# MCU.net
KiCad netlist of a schematic drawn in Altium Designer
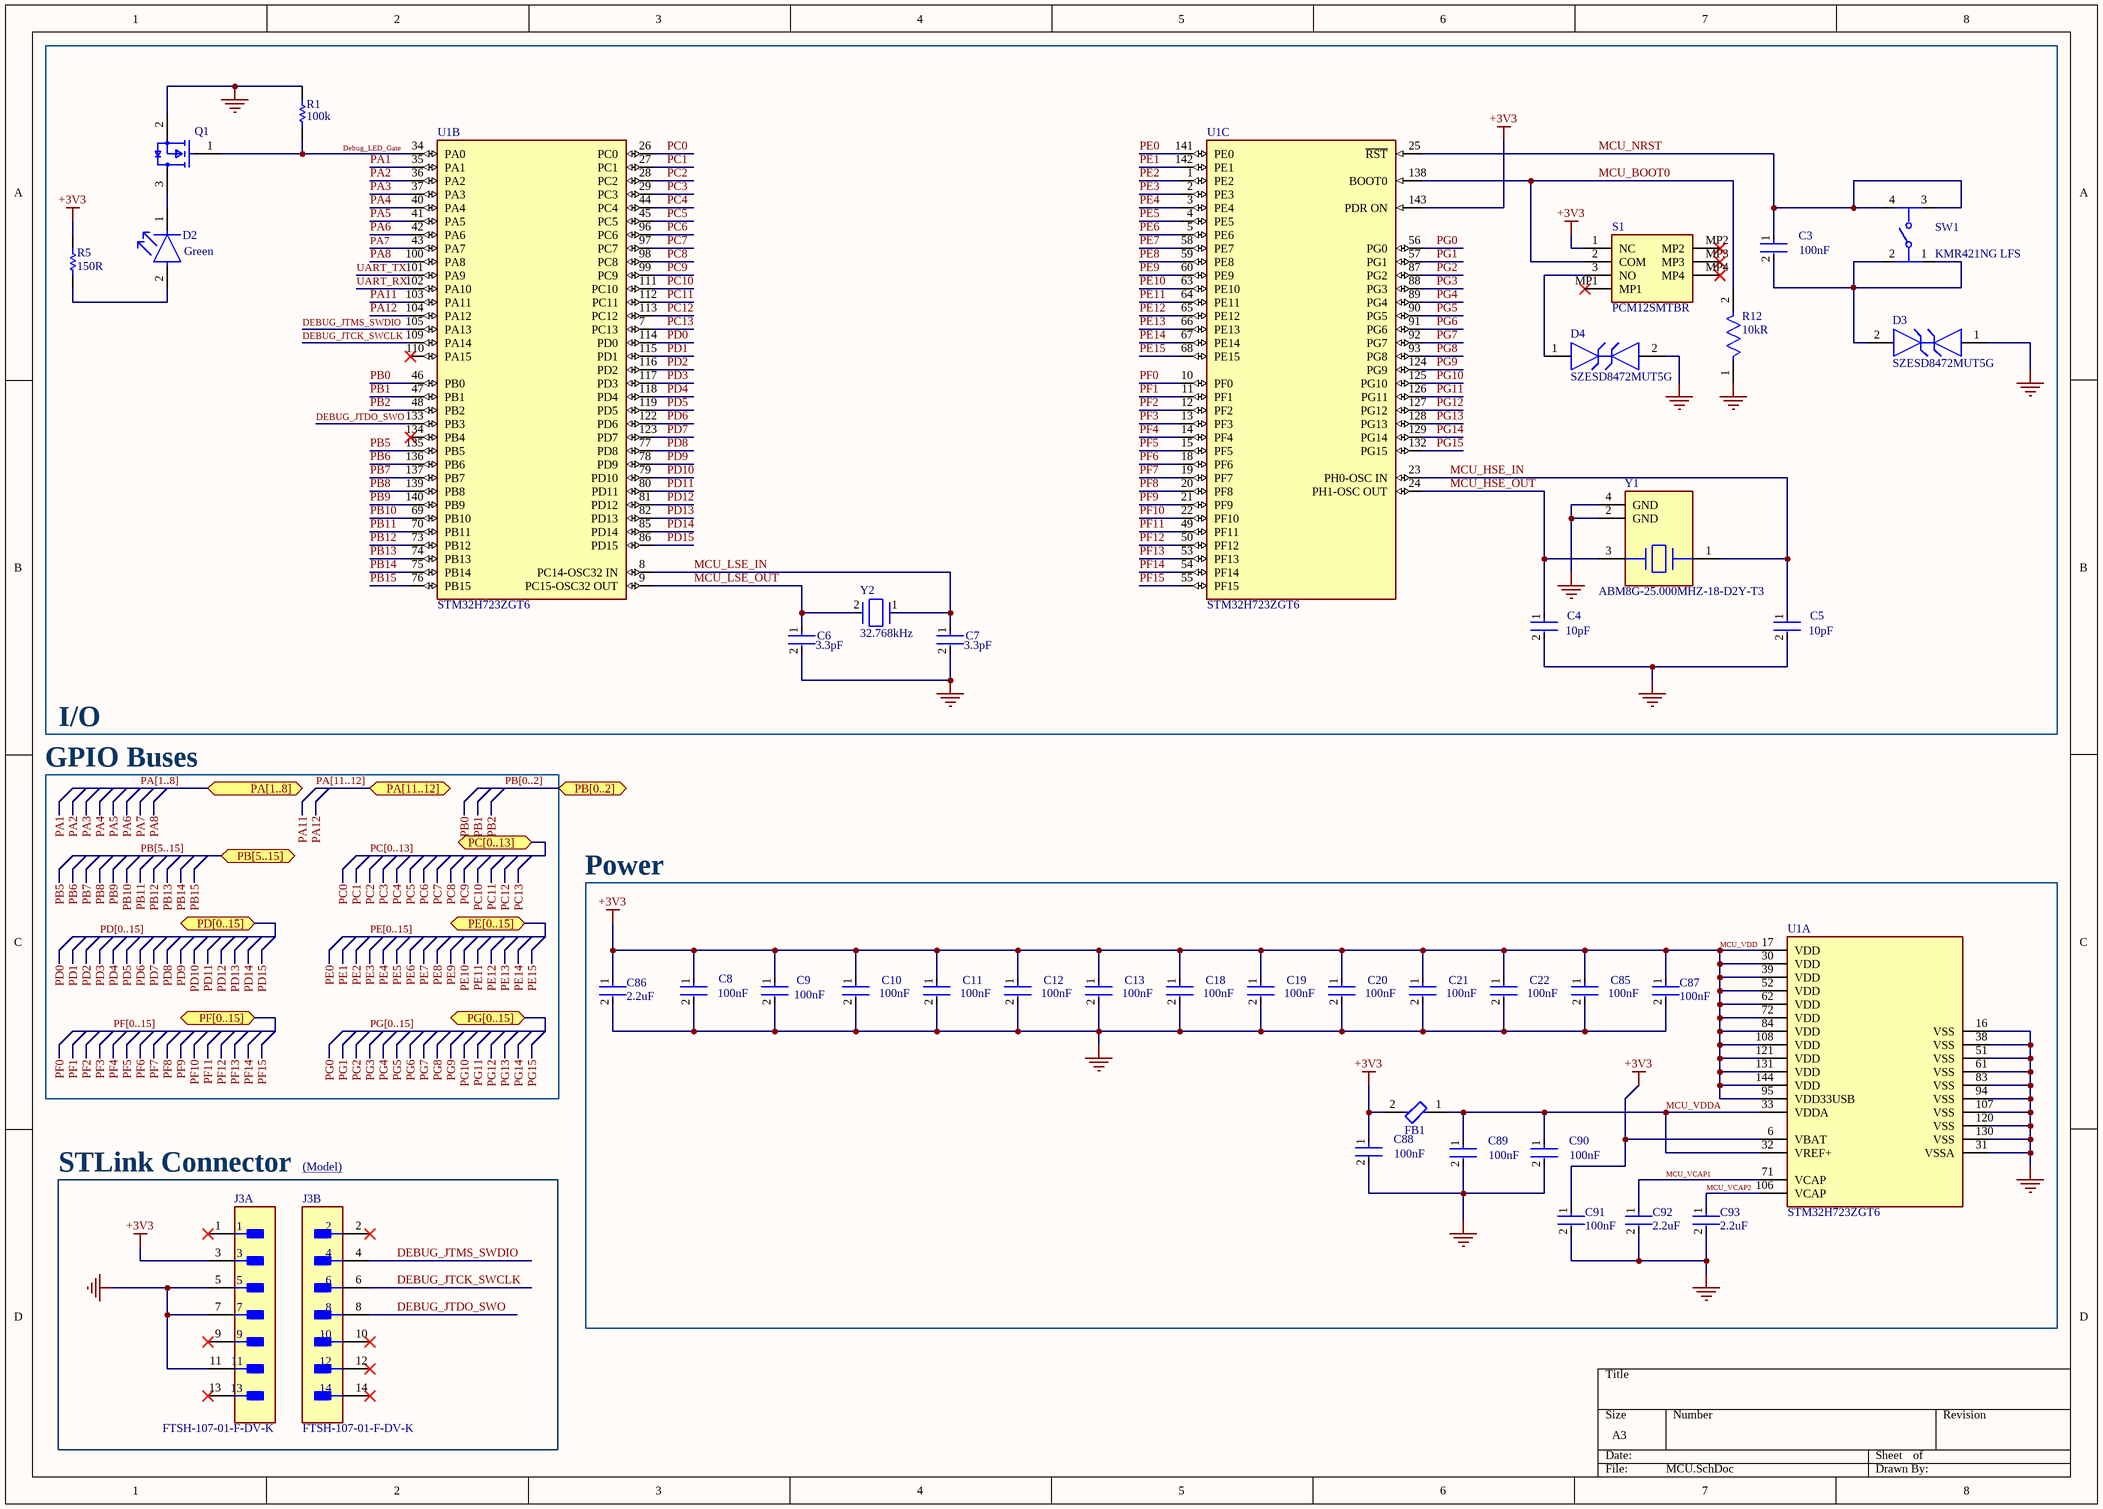
[diagram p0: MCU.SchDoc]

(export (version "E")
  (design (tool "Eeschema 10.0.6"))
  (components
    (comp (ref "C3")
      (value "GCM155R71H104ME02J")
      (footprint "FP-GCM155-0_05-IPC_A")
      (description "Ceramic Capacitor for Automotive 100nF ±20% 50VDC X7R 0402 Paper T/R")
      (fields (field (name "CAPACITANCE") "100nF"))
      (libsource (lib "Altium Content Vault") (part "02cd4be3c70576c341d710602a673aa"))
    )
    (comp (ref "C4")
      (value "GCM1555G1H100GA16D")
      (footprint "FP-GCM155-0_05-IPC_B")
      (description "Ceramic Capacitor for Automotive 10pF ±2% 50VDC X8G 0402 Paper T/R")
      (fields (field (name "CAPACITANCE") "10pF"))
      (libsource (lib "Altium Content Vault") (part "02cd4be3c70576c341d710602a673aa"))
    )
    (comp (ref "C5")
      (value "GCM1555G1H100GA16D")
      (footprint "FP-GCM155-0_05-IPC_B")
      (description "Ceramic Capacitor for Automotive 10pF ±2% 50VDC X8G 0402 Paper T/R")
      (fields (field (name "CAPACITANCE") "10pF"))
      (libsource (lib "Altium Content Vault") (part "02cd4be3c70576c341d710602a673aa"))
    )
    (comp (ref "C6")
      (value "GCM1555C1H3R3CA16J")
      (footprint "FP-GCM155-0_05-IPC_C")
      (description "Ceramic Capacitor for Automotive 3.3pF ±0.25pF 50VDC C0G 0402 Paper T/R")
      (fields (field (name "CAPACITANCE") "3.3pF"))
      (libsource (lib "Altium Content Vault") (part "02cd4be3c70576c341d710602a673aa"))
    )
    (comp (ref "C7")
      (value "GCM1555C1H3R3CA16J")
      (footprint "FP-GCM155-0_05-IPC_C")
      (description "Ceramic Capacitor for Automotive 3.3pF ±0.25pF 50VDC C0G 0402 Paper T/R")
      (fields (field (name "CAPACITANCE") "3.3pF"))
      (libsource (lib "Altium Content Vault") (part "02cd4be3c70576c341d710602a673aa"))
    )
    (comp (ref "C8")
      (value "GCM155R71H104ME02J")
      (footprint "FP-GCM155-0_05-IPC_A")
      (description "Ceramic Capacitor for Automotive 100nF ±20% 50VDC X7R 0402 Paper T/R")
      (fields (field (name "CAPACITANCE") "100nF"))
      (libsource (lib "Altium Content Vault") (part "02cd4be3c70576c341d710602a673aa"))
    )
    (comp (ref "C9")
      (value "GCM155R71H104ME02J")
      (footprint "FP-GCM155-0_05-IPC_A")
      (description "Ceramic Capacitor for Automotive 100nF ±20% 50VDC X7R 0402 Paper T/R")
      (fields (field (name "CAPACITANCE") "100nF"))
      (libsource (lib "Altium Content Vault") (part "02cd4be3c70576c341d710602a673aa"))
    )
    (comp (ref "C10")
      (value "GCM155R71H104ME02J")
      (footprint "FP-GCM155-0_05-IPC_A")
      (description "Ceramic Capacitor for Automotive 100nF ±20% 50VDC X7R 0402 Paper T/R")
      (fields (field (name "CAPACITANCE") "100nF"))
      (libsource (lib "Altium Content Vault") (part "02cd4be3c70576c341d710602a673aa"))
    )
    (comp (ref "C11")
      (value "GCM155R71H104ME02J")
      (footprint "FP-GCM155-0_05-IPC_A")
      (description "Ceramic Capacitor for Automotive 100nF ±20% 50VDC X7R 0402 Paper T/R")
      (fields (field (name "CAPACITANCE") "100nF"))
      (libsource (lib "Altium Content Vault") (part "02cd4be3c70576c341d710602a673aa"))
    )
    (comp (ref "C12")
      (value "GCM155R71H104ME02J")
      (footprint "FP-GCM155-0_05-IPC_A")
      (description "Ceramic Capacitor for Automotive 100nF ±20% 50VDC X7R 0402 Paper T/R")
      (fields (field (name "CAPACITANCE") "100nF"))
      (libsource (lib "Altium Content Vault") (part "02cd4be3c70576c341d710602a673aa"))
    )
    (comp (ref "C13")
      (value "GCM155R71H104ME02J")
      (footprint "FP-GCM155-0_05-IPC_A")
      (description "Ceramic Capacitor for Automotive 100nF ±20% 50VDC X7R 0402 Paper T/R")
      (fields (field (name "CAPACITANCE") "100nF"))
      (libsource (lib "Altium Content Vault") (part "02cd4be3c70576c341d710602a673aa"))
    )
    (comp (ref "C18")
      (value "GCM155R71H104ME02J")
      (footprint "FP-GCM155-0_05-IPC_A")
      (description "Ceramic Capacitor for Automotive 100nF ±20% 50VDC X7R 0402 Paper T/R")
      (fields (field (name "CAPACITANCE") "100nF"))
      (libsource (lib "Altium Content Vault") (part "02cd4be3c70576c341d710602a673aa"))
    )
    (comp (ref "C19")
      (value "GCM155R71H104ME02J")
      (footprint "FP-GCM155-0_05-IPC_A")
      (description "Ceramic Capacitor for Automotive 100nF ±20% 50VDC X7R 0402 Paper T/R")
      (fields (field (name "CAPACITANCE") "100nF"))
      (libsource (lib "Altium Content Vault") (part "02cd4be3c70576c341d710602a673aa"))
    )
    (comp (ref "C20")
      (value "GCM155R71H104ME02J")
      (footprint "FP-GCM155-0_05-IPC_A")
      (description "Ceramic Capacitor for Automotive 100nF ±20% 50VDC X7R 0402 Paper T/R")
      (fields (field (name "CAPACITANCE") "100nF"))
      (libsource (lib "Altium Content Vault") (part "02cd4be3c70576c341d710602a673aa"))
    )
    (comp (ref "C21")
      (value "GCM155R71H104ME02J")
      (footprint "FP-GCM155-0_05-IPC_A")
      (description "Ceramic Capacitor for Automotive 100nF ±20% 50VDC X7R 0402 Paper T/R")
      (fields (field (name "CAPACITANCE") "100nF"))
      (libsource (lib "Altium Content Vault") (part "02cd4be3c70576c341d710602a673aa"))
    )
    (comp (ref "C22")
      (value "GCM155R71H104ME02J")
      (footprint "FP-GCM155-0_05-IPC_A")
      (description "Ceramic Capacitor for Automotive 100nF ±20% 50VDC X7R 0402 Paper T/R")
      (fields (field (name "CAPACITANCE") "100nF"))
      (libsource (lib "Altium Content Vault") (part "02cd4be3c70576c341d710602a673aa"))
    )
    (comp (ref "C85")
      (value "GCM155R71H104ME02J")
      (footprint "FP-GCM155-0_05-IPC_A")
      (description "Ceramic Capacitor for Automotive 100nF ±20% 50VDC X7R 0402 Paper T/R")
      (fields (field (name "CAPACITANCE") "100nF"))
      (libsource (lib "Altium Content Vault") (part "02cd4be3c70576c341d710602a673aa"))
    )
    (comp (ref "C86")
      (value "GCM188C71A225KE02D")
      (footprint "FP-GCH188-0_1-e0_2_0_5-MFG")
      (description "GCM188C71A225KE02D Multilayer Ceramic Capacitor, 2.2 uF, 10 V, ± 10%, X7S, 0603 [1608 Metric]")
      (fields (field (name "CAPACITANCE") "2.2uF"))
      (libsource (lib "Altium Content Vault") (part "b4654b650e69147ec39a6b967a45e02"))
    )
    (comp (ref "C87")
      (value "GCM155R71H104ME02J")
      (footprint "FP-GCM155-0_05-IPC_A")
      (description "Ceramic Capacitor for Automotive 100nF ±20% 50VDC X7R 0402 Paper T/R")
      (fields (field (name "CAPACITANCE") "100nF"))
      (libsource (lib "Altium Content Vault") (part "02cd4be3c70576c341d710602a673aa"))
    )
    (comp (ref "C88")
      (value "GCM155R71H104ME02J")
      (footprint "FP-GCM155-0_05-IPC_A")
      (description "Ceramic Capacitor for Automotive 100nF ±20% 50VDC X7R 0402 Paper T/R")
      (fields (field (name "CAPACITANCE") "100nF"))
      (libsource (lib "Altium Content Vault") (part "02cd4be3c70576c341d710602a673aa"))
    )
    (comp (ref "C89")
      (value "GCM155R71H104ME02J")
      (footprint "FP-GCM155-0_05-IPC_A")
      (description "Ceramic Capacitor for Automotive 100nF ±20% 50VDC X7R 0402 Paper T/R")
      (fields (field (name "CAPACITANCE") "100nF"))
      (libsource (lib "Altium Content Vault") (part "02cd4be3c70576c341d710602a673aa"))
    )
    (comp (ref "C90")
      (value "GCM155R71H104ME02J")
      (footprint "FP-GCM155-0_05-IPC_A")
      (description "Ceramic Capacitor for Automotive 100nF ±20% 50VDC X7R 0402 Paper T/R")
      (fields (field (name "CAPACITANCE") "100nF"))
      (libsource (lib "Altium Content Vault") (part "02cd4be3c70576c341d710602a673aa"))
    )
    (comp (ref "C91")
      (value "GCM155R71H104ME02J")
      (footprint "FP-GCM155-0_05-IPC_A")
      (description "Ceramic Capacitor for Automotive 100nF ±20% 50VDC X7R 0402 Paper T/R")
      (fields (field (name "CAPACITANCE") "100nF"))
      (libsource (lib "Altium Content Vault") (part "02cd4be3c70576c341d710602a673aa"))
    )
    (comp (ref "C92")
      (value "GCM188C71A225KE02D")
      (footprint "FP-GCH188-0_1-e0_2_0_5-MFG")
      (description "GCM188C71A225KE02D Multilayer Ceramic Capacitor, 2.2 uF, 10 V, ± 10%, X7S, 0603 [1608 Metric]")
      (fields (field (name "CAPACITANCE") "2.2uF"))
      (libsource (lib "Altium Content Vault") (part "b4654b650e69147ec39a6b967a45e02"))
    )
    (comp (ref "C93")
      (value "GCM188C71A225KE02D")
      (footprint "FP-GCH188-0_1-e0_2_0_5-MFG")
      (description "GCM188C71A225KE02D Multilayer Ceramic Capacitor, 2.2 uF, 10 V, ± 10%, X7S, 0603 [1608 Metric]")
      (fields (field (name "CAPACITANCE") "2.2uF"))
      (libsource (lib "Altium Content Vault") (part "b4654b650e69147ec39a6b967a45e02"))
    )
    (comp (ref "D2")
      (value "SML-P13PTT86R")
      (footprint "FP-SML-P1-MFG")
      (description "LED GREEN CLEAR 1006 SMD")
      (fields
        (field (name "MANUFACTURER") "Rohm")
        (field (name "OCTOPART") "https://octopart.com/sml-p13ptt86r-rohm-59370256")
        (field (name "COLOUR") "Green")
      )
      (libsource (lib "Altium Content Vault") (part "8706943c75ba83719d021d2fdc84c58"))
    )
    (comp (ref "D3")
      (value "SZESD8472MUT5G")
      (footprint "FP-152AF-MFG")
      (description "TVS DIODE 5.3V 14V 2X3DFN")
      (libsource (lib "Altium Content Vault") (part "9a4650ba5e636bd8b2e4c4fb393e9aa"))
    )
    (comp (ref "D4")
      (value "SZESD8472MUT5G")
      (footprint "FP-152AF-MFG")
      (description "TVS DIODE 5.3V 14V 2X3DFN")
      (libsource (lib "Altium Content Vault") (part "9a4650ba5e636bd8b2e4c4fb393e9aa"))
    )
    (comp (ref "FB1")
      (value "BLM15BX102SZ1D")
      (footprint "FP-BLM15-0_05-MFG")
      (description "Chip Ferrite Bead, 0402, 1000Ω @ 100MHz, 0.65Ω, 25%, 300mA")
      (libsource (lib "Altium Content Vault") (part "5f30dd21d616792df468990f7003faa"))
    )
    (comp (ref "J3")
      (value "FTSH-107-01-F-DV-K")
      (footprint "FP-FTSH-107-01-F-DV-K-MFG")
      (description "CONN HEADER SMD 14POS 1.27MM")
      (libsource (lib "") (part "ab214579d66ef07f87fa9c6f4e4f9ab_1"))
    )
    (comp (ref "Q1")
      (value "2N7002H6327XTSA2")
      (footprint "FP-PG-SOT23-3-MFG")
      (description "MOSFET N-CH 60V 0.3A SOT23")
      (libsource (lib "Altium Content Vault") (part "2d979dc9c009d20783d0745ce0ba7b4"))
    )
    (comp (ref "R1")
      (value "RC0402FR-07100KL")
      (footprint "RESC1005X40X25NL05T10")
      (fields (field (name "MANUFACTURER") "Yageo / Phycomp") (field (name "RESISTANCE") "100k"))
      (libsource (lib "Altium Content Vault") (part "RES"))
    )
    (comp (ref "R5")
      (value "RC0402JR-13150RL")
      (footprint "RESC1005X40X25LL05T10")
      (fields (field (name "MANUFACTURER") "Yageo") (field (name "RESISTANCE") "150R"))
      (libsource (lib "Altium Content Vault") (part "RES"))
    )
    (comp (ref "R12")
      (value "RC0402FR-1310KL")
      (footprint "FP-RC0402-0_4-IPC_A")
      (description "RESISTOR 0402 10K 1%")
      (fields (field (name "RESISTANCE") "10kR") (field (name "TOLERANCE") "1%"))
      (libsource (lib "Altium Content Vault") (part "1029c3af85768c4190bb7ad29bc67b5"))
    )
    (comp (ref "S1")
      (value "PCM12SMTBR")
      (footprint "PCM12SMTBR")
      (description "Switch")
      (fields (field (name "MOUSER PART NUMBER") "611-PCM12SMTBR"))
      (libsource (lib "audio_dev_pcb") (part "PCM12SMTBR"))
    )
    (comp (ref "SW1")
      (value "KMR421NG LFS")
      (footprint "FP-KMR421NG_LFS-MFG")
      (description "SWITCH TACTILE SPST-NO 0.05A 32V")
      (fields
        (field (name "MANUFACTURER") "C&K Components")
        (field (name "OCTOPART") "https://octopart.com/kmr421nglfs-c%26k+components-7226706")
      )
      (libsource (lib "Altium Content Vault") (part "82b636f13fd696edb7519609c0a8a76"))
    )
    (comp (ref "U1")
      (value "STM32H723ZGT6")
      (footprint "FP-LQFP144-1A-IPC_A")
      (description "IC MCU 32BIT 1MB FLASH 144LQFP")
      (libsource (lib "") (part "099c9e622ff36f7eb897f9cba6d1f51_1"))
    )
    (comp (ref "Y1")
      (value "ABM8G-25.000MHZ-18-D2Y-T3")
      (footprint "FP-ABM8G-MFG")
      (description "Crystal 25MHz ±20ppm (Tol) ±30ppm (Stability) 18pF FUND 60Ω 4-Pin SMD T/R")
      (fields (field (name "TOLERANCE") "20ppm"))
      (libsource (lib "Altium Content Vault") (part "48e526d86b7f2615d98721063c72f49"))
    )
    (comp (ref "Y2")
      (value "ECS-.327-6-34QCN-TR")
      (footprint "FP-ECX-34Q-MFG")
      (description "CRYSTAL 32.768KHZ 6PF SMD")
      (fields
        (field (name "OCTOPART") "https://octopart.com/ecs-.327-6-34qcn-tr-ecs+international-97157707")
        (field (name "MANUFACTURER") "ECS Inc.")
        (field (name "FREQUENCY") "32.768kHz")
      )
      (libsource (lib "Altium Content Vault") (part "99724985039315a44fd0d1401b84e49"))
    )
  )
  (nets
    (net (code "1") (name "+3V3") (class "Default")
      (node (ref "C10") (pin "1") (pinfunction "1_1") (pintype "passive"))
      (node (ref "C11") (pin "1") (pinfunction "1_1") (pintype "passive"))
      (node (ref "C12") (pin "1") (pinfunction "1_1") (pintype "passive"))
      (node (ref "C13") (pin "1") (pinfunction "1_1") (pintype "passive"))
      (node (ref "C18") (pin "1") (pinfunction "1_1") (pintype "passive"))
      (node (ref "C19") (pin "1") (pinfunction "1_1") (pintype "passive"))
      (node (ref "C20") (pin "1") (pinfunction "1_1") (pintype "passive"))
      (node (ref "C21") (pin "1") (pinfunction "1_1") (pintype "passive"))
      (node (ref "C22") (pin "1") (pinfunction "1_1") (pintype "passive"))
      (node (ref "C8") (pin "1") (pinfunction "1_1") (pintype "passive"))
      (node (ref "C85") (pin "1") (pinfunction "1_1") (pintype "passive"))
      (node (ref "C86") (pin "1") (pinfunction "1_1") (pintype "passive"))
      (node (ref "C87") (pin "1") (pinfunction "1_1") (pintype "passive"))
      (node (ref "C88") (pin "1") (pinfunction "1_1") (pintype "passive"))
      (node (ref "C9") (pin "1") (pinfunction "1_1") (pintype "passive"))
      (node (ref "C91") (pin "1") (pinfunction "1_1") (pintype "passive"))
      (node (ref "FB1") (pin "2") (pinfunction "2_2") (pintype "passive"))
      (node (ref "J3") (pin "3") (pinfunction "3_3") (pintype "passive"))
      (node (ref "R5") (pin "2") (pinfunction "2_2") (pintype "passive"))
      (node (ref "S1") (pin "1") (pinfunction "NC_1") (pintype "passive"))
      (node (ref "U1") (pin "108") (pinfunction "VDD_108") (pintype "power_in"))
      (node (ref "U1") (pin "121") (pinfunction "VDD_121") (pintype "power_in"))
      (node (ref "U1") (pin "131") (pinfunction "VDD_131") (pintype "power_in"))
      (node (ref "U1") (pin "143") (pinfunction "PDR_ON_143") (pintype "input"))
      (node (ref "U1") (pin "144") (pinfunction "VDD_144") (pintype "power_in"))
      (node (ref "U1") (pin "17") (pinfunction "VDD_17") (pintype "power_in"))
      (node (ref "U1") (pin "30") (pinfunction "VDD_30") (pintype "power_in"))
      (node (ref "U1") (pin "39") (pinfunction "VDD_39") (pintype "power_in"))
      (node (ref "U1") (pin "52") (pinfunction "VDD_52") (pintype "power_in"))
      (node (ref "U1") (pin "6") (pinfunction "VBAT_6") (pintype "power_in"))
      (node (ref "U1") (pin "62") (pinfunction "VDD_62") (pintype "power_in"))
      (node (ref "U1") (pin "72") (pinfunction "VDD_72") (pintype "power_in"))
      (node (ref "U1") (pin "84") (pinfunction "VDD_84") (pintype "power_in"))
      (node (ref "U1") (pin "95") (pinfunction "VDD33USB_95") (pintype "power_in"))
    )
    (net (code "2") (name "/DEBUG_JTCK_SWCLK") (class "Default")
      (node (ref "J3") (pin "6") (pinfunction "6_6") (pintype "passive"))
      (node (ref "U1") (pin "109") (pinfunction "PA14_109") (pintype "bidirectional"))
    )
    (net (code "3") (name "/DEBUG_JTDO_SWO") (class "Default")
      (node (ref "J3") (pin "8") (pinfunction "8_8") (pintype "passive"))
      (node (ref "U1") (pin "133") (pinfunction "PB3_133") (pintype "bidirectional"))
    )
    (net (code "4") (name "/DEBUG_JTMS_SWDIO") (class "Default")
      (node (ref "J3") (pin "4") (pinfunction "4_4") (pintype "passive"))
      (node (ref "U1") (pin "105") (pinfunction "PA13_105") (pintype "bidirectional"))
    )
    (net (code "5") (name "/Debug_LED_Gate") (class "Default")
      (node (ref "Q1") (pin "1") (pinfunction "gate_1") (pintype "passive"))
      (node (ref "R1") (pin "1") (pinfunction "1_1") (pintype "passive"))
      (node (ref "U1") (pin "34") (pinfunction "PA0_34") (pintype "bidirectional"))
    )
    (net (code "6") (name "/MCU_BOOT0") (class "Default")
      (node (ref "R12") (pin "2") (pinfunction "2_2") (pintype "passive"))
      (node (ref "S1") (pin "2") (pinfunction "COM_2") (pintype "passive"))
      (node (ref "U1") (pin "138") (pinfunction "BOOT0_138") (pintype "input"))
    )
    (net (code "7") (name "/MCU_HSE_IN") (class "Default")
      (node (ref "C5") (pin "1") (pinfunction "1_1") (pintype "passive"))
      (node (ref "U1") (pin "23") (pinfunction "PH0-OSC_IN_23") (pintype "bidirectional"))
      (node (ref "Y1") (pin "1") (pinfunction "1_1") (pintype "passive"))
    )
    (net (code "8") (name "/MCU_HSE_OUT") (class "Default")
      (node (ref "C4") (pin "1") (pinfunction "1_1") (pintype "passive"))
      (node (ref "U1") (pin "24") (pinfunction "PH1-OSC_OUT_24") (pintype "bidirectional"))
      (node (ref "Y1") (pin "3") (pinfunction "3_3") (pintype "passive"))
    )
    (net (code "9") (name "/MCU_LSE_IN") (class "Default")
      (node (ref "C7") (pin "1") (pinfunction "1_1") (pintype "passive"))
      (node (ref "U1") (pin "8") (pinfunction "PC14-OSC32_IN_8") (pintype "bidirectional"))
      (node (ref "Y2") (pin "1") (pinfunction "In/Out_1") (pintype "passive"))
    )
    (net (code "10") (name "/MCU_LSE_OUT") (class "Default")
      (node (ref "C6") (pin "1") (pinfunction "1_1") (pintype "passive"))
      (node (ref "U1") (pin "9") (pinfunction "PC15-OSC32_OUT_9") (pintype "bidirectional"))
      (node (ref "Y2") (pin "2") (pinfunction "Out/In_2") (pintype "passive"))
    )
    (net (code "11") (name "/MCU_NRST") (class "Default")
      (node (ref "C3") (pin "1") (pinfunction "1_1") (pintype "passive"))
      (node (ref "SW1") (pin "3") (pinfunction "3_3") (pintype "passive"))
      (node (ref "SW1") (pin "4") (pinfunction "4_4") (pintype "passive"))
      (node (ref "U1") (pin "25") (pinfunction "~{RST}_25") (pintype "input"))
    )
    (net (code "12") (name "/MCU_VCAP1") (class "Default")
      (node (ref "C92") (pin "1") (pinfunction "1_1") (pintype "passive"))
      (node (ref "U1") (pin "71") (pinfunction "VCAP_71") (pintype "power_in"))
    )
    (net (code "13") (name "/MCU_VCAP2") (class "Default")
      (node (ref "C93") (pin "1") (pinfunction "1_1") (pintype "passive"))
      (node (ref "U1") (pin "106") (pinfunction "VCAP_106") (pintype "power_in"))
    )
    (net (code "14") (name "/MCU_VDDA") (class "Default")
      (node (ref "C89") (pin "1") (pinfunction "1_1") (pintype "passive"))
      (node (ref "C90") (pin "1") (pinfunction "1_1") (pintype "passive"))
      (node (ref "FB1") (pin "1") (pinfunction "1_1") (pintype "passive"))
      (node (ref "U1") (pin "32") (pinfunction "VREF+_32") (pintype "power_in"))
      (node (ref "U1") (pin "33") (pinfunction "VDDA_33") (pintype "power_in"))
    )
    (net (code "15") (name "/PA1") (class "Default")
      (node (ref "U1") (pin "35") (pinfunction "PA1_35") (pintype "bidirectional"))
    )
    (net (code "16") (name "/PA2") (class "Default")
      (node (ref "U1") (pin "36") (pinfunction "PA2_36") (pintype "bidirectional"))
    )
    (net (code "17") (name "/PA3") (class "Default")
      (node (ref "U1") (pin "37") (pinfunction "PA3_37") (pintype "bidirectional"))
    )
    (net (code "18") (name "/PA4") (class "Default")
      (node (ref "U1") (pin "40") (pinfunction "PA4_40") (pintype "bidirectional"))
    )
    (net (code "19") (name "/PA5") (class "Default")
      (node (ref "U1") (pin "41") (pinfunction "PA5_41") (pintype "bidirectional"))
    )
    (net (code "20") (name "/PA6") (class "Default")
      (node (ref "U1") (pin "42") (pinfunction "PA6_42") (pintype "bidirectional"))
    )
    (net (code "21") (name "/PA7") (class "Default")
      (node (ref "U1") (pin "43") (pinfunction "PA7_43") (pintype "bidirectional"))
    )
    (net (code "22") (name "/PA8") (class "Default")
      (node (ref "U1") (pin "100") (pinfunction "PA8_100") (pintype "bidirectional"))
    )
    (net (code "23") (name "/PA11") (class "Default")
      (node (ref "U1") (pin "103") (pinfunction "PA11_103") (pintype "bidirectional"))
    )
    (net (code "24") (name "/PA12") (class "Default")
      (node (ref "U1") (pin "104") (pinfunction "PA12_104") (pintype "bidirectional"))
    )
    (net (code "27") (name "/PB0") (class "Default")
      (node (ref "U1") (pin "46") (pinfunction "PB0_46") (pintype "bidirectional"))
    )
    (net (code "28") (name "/PB1") (class "Default")
      (node (ref "U1") (pin "47") (pinfunction "PB1_47") (pintype "bidirectional"))
    )
    (net (code "29") (name "/PB2") (class "Default")
      (node (ref "U1") (pin "48") (pinfunction "PB2_48") (pintype "bidirectional"))
    )
    (net (code "30") (name "/PB5") (class "Default")
      (node (ref "U1") (pin "135") (pinfunction "PB5_135") (pintype "bidirectional"))
    )
    (net (code "31") (name "/PB6") (class "Default")
      (node (ref "U1") (pin "136") (pinfunction "PB6_136") (pintype "bidirectional"))
    )
    (net (code "32") (name "/PB7") (class "Default")
      (node (ref "U1") (pin "137") (pinfunction "PB7_137") (pintype "bidirectional"))
    )
    (net (code "33") (name "/PB8") (class "Default")
      (node (ref "U1") (pin "139") (pinfunction "PB8_139") (pintype "bidirectional"))
    )
    (net (code "34") (name "/PB9") (class "Default")
      (node (ref "U1") (pin "140") (pinfunction "PB9_140") (pintype "bidirectional"))
    )
    (net (code "35") (name "/PB10") (class "Default")
      (node (ref "U1") (pin "69") (pinfunction "PB10_69") (pintype "bidirectional"))
    )
    (net (code "36") (name "/PB11") (class "Default")
      (node (ref "U1") (pin "70") (pinfunction "PB11_70") (pintype "bidirectional"))
    )
    (net (code "37") (name "/PB12") (class "Default")
      (node (ref "U1") (pin "73") (pinfunction "PB12_73") (pintype "bidirectional"))
    )
    (net (code "38") (name "/PB13") (class "Default")
      (node (ref "U1") (pin "74") (pinfunction "PB13_74") (pintype "bidirectional"))
    )
    (net (code "39") (name "/PB14") (class "Default")
      (node (ref "U1") (pin "75") (pinfunction "PB14_75") (pintype "bidirectional"))
    )
    (net (code "40") (name "/PB15") (class "Default")
      (node (ref "U1") (pin "76") (pinfunction "PB15_76") (pintype "bidirectional"))
    )
    (net (code "43") (name "/PC0") (class "Default")
      (node (ref "U1") (pin "26") (pinfunction "PC0_26") (pintype "bidirectional"))
    )
    (net (code "44") (name "/PC1") (class "Default")
      (node (ref "U1") (pin "27") (pinfunction "PC1_27") (pintype "bidirectional"))
    )
    (net (code "45") (name "/PC2") (class "Default")
      (node (ref "U1") (pin "28") (pinfunction "PC2_28") (pintype "bidirectional"))
    )
    (net (code "46") (name "/PC3") (class "Default")
      (node (ref "U1") (pin "29") (pinfunction "PC3_29") (pintype "bidirectional"))
    )
    (net (code "47") (name "/PC4") (class "Default")
      (node (ref "U1") (pin "44") (pinfunction "PC4_44") (pintype "bidirectional"))
    )
    (net (code "48") (name "/PC5") (class "Default")
      (node (ref "U1") (pin "45") (pinfunction "PC5_45") (pintype "bidirectional"))
    )
    (net (code "49") (name "/PC6") (class "Default")
      (node (ref "U1") (pin "96") (pinfunction "PC6_96") (pintype "bidirectional"))
    )
    (net (code "50") (name "/PC7") (class "Default")
      (node (ref "U1") (pin "97") (pinfunction "PC7_97") (pintype "bidirectional"))
    )
    (net (code "51") (name "/PC8") (class "Default")
      (node (ref "U1") (pin "98") (pinfunction "PC8_98") (pintype "bidirectional"))
    )
    (net (code "52") (name "/PC9") (class "Default")
      (node (ref "U1") (pin "99") (pinfunction "PC9_99") (pintype "bidirectional"))
    )
    (net (code "53") (name "/PC10") (class "Default")
      (node (ref "U1") (pin "111") (pinfunction "PC10_111") (pintype "bidirectional"))
    )
    (net (code "54") (name "/PC11") (class "Default")
      (node (ref "U1") (pin "112") (pinfunction "PC11_112") (pintype "bidirectional"))
    )
    (net (code "55") (name "/PC12") (class "Default")
      (node (ref "U1") (pin "113") (pinfunction "PC12_113") (pintype "bidirectional"))
    )
    (net (code "56") (name "/PC13") (class "Default")
      (node (ref "U1") (pin "7") (pinfunction "PC13_7") (pintype "bidirectional"))
    )
    (net (code "58") (name "/PD0") (class "Default")
      (node (ref "U1") (pin "114") (pinfunction "PD0_114") (pintype "bidirectional"))
    )
    (net (code "59") (name "/PD1") (class "Default")
      (node (ref "U1") (pin "115") (pinfunction "PD1_115") (pintype "bidirectional"))
    )
    (net (code "60") (name "/PD2") (class "Default")
      (node (ref "U1") (pin "116") (pinfunction "PD2_116") (pintype "bidirectional"))
    )
    (net (code "61") (name "/PD3") (class "Default")
      (node (ref "U1") (pin "117") (pinfunction "PD3_117") (pintype "bidirectional"))
    )
    (net (code "62") (name "/PD4") (class "Default")
      (node (ref "U1") (pin "118") (pinfunction "PD4_118") (pintype "bidirectional"))
    )
    (net (code "63") (name "/PD5") (class "Default")
      (node (ref "U1") (pin "119") (pinfunction "PD5_119") (pintype "bidirectional"))
    )
    (net (code "64") (name "/PD6") (class "Default")
      (node (ref "U1") (pin "122") (pinfunction "PD6_122") (pintype "bidirectional"))
    )
    (net (code "65") (name "/PD7") (class "Default")
      (node (ref "U1") (pin "123") (pinfunction "PD7_123") (pintype "bidirectional"))
    )
    (net (code "66") (name "/PD8") (class "Default")
      (node (ref "U1") (pin "77") (pinfunction "PD8_77") (pintype "bidirectional"))
    )
    (net (code "67") (name "/PD9") (class "Default")
      (node (ref "U1") (pin "78") (pinfunction "PD9_78") (pintype "bidirectional"))
    )
    (net (code "68") (name "/PD10") (class "Default")
      (node (ref "U1") (pin "79") (pinfunction "PD10_79") (pintype "bidirectional"))
    )
    (net (code "69") (name "/PD11") (class "Default")
      (node (ref "U1") (pin "80") (pinfunction "PD11_80") (pintype "bidirectional"))
    )
    (net (code "70") (name "/PD12") (class "Default")
      (node (ref "U1") (pin "81") (pinfunction "PD12_81") (pintype "bidirectional"))
    )
    (net (code "71") (name "/PD13") (class "Default")
      (node (ref "U1") (pin "82") (pinfunction "PD13_82") (pintype "bidirectional"))
    )
    (net (code "72") (name "/PD14") (class "Default")
      (node (ref "U1") (pin "85") (pinfunction "PD14_85") (pintype "bidirectional"))
    )
    (net (code "73") (name "/PD15") (class "Default")
      (node (ref "U1") (pin "86") (pinfunction "PD15_86") (pintype "bidirectional"))
    )
    (net (code "75") (name "/PE0") (class "Default")
      (node (ref "U1") (pin "141") (pinfunction "PE0_141") (pintype "bidirectional"))
    )
    (net (code "76") (name "/PE1") (class "Default")
      (node (ref "U1") (pin "142") (pinfunction "PE1_142") (pintype "bidirectional"))
    )
    (net (code "77") (name "/PE2") (class "Default")
      (node (ref "U1") (pin "1") (pinfunction "PE2_1") (pintype "bidirectional"))
    )
    (net (code "78") (name "/PE3") (class "Default")
      (node (ref "U1") (pin "2") (pinfunction "PE3_2") (pintype "bidirectional"))
    )
    (net (code "79") (name "/PE4") (class "Default")
      (node (ref "U1") (pin "3") (pinfunction "PE4_3") (pintype "bidirectional"))
    )
    (net (code "80") (name "/PE5") (class "Default")
      (node (ref "U1") (pin "4") (pinfunction "PE5_4") (pintype "bidirectional"))
    )
    (net (code "81") (name "/PE6") (class "Default")
      (node (ref "U1") (pin "5") (pinfunction "PE6_5") (pintype "bidirectional"))
    )
    (net (code "82") (name "/PE7") (class "Default")
      (node (ref "U1") (pin "58") (pinfunction "PE7_58") (pintype "bidirectional"))
    )
    (net (code "83") (name "/PE8") (class "Default")
      (node (ref "U1") (pin "59") (pinfunction "PE8_59") (pintype "bidirectional"))
    )
    (net (code "84") (name "/PE9") (class "Default")
      (node (ref "U1") (pin "60") (pinfunction "PE9_60") (pintype "bidirectional"))
    )
    (net (code "85") (name "/PE10") (class "Default")
      (node (ref "U1") (pin "63") (pinfunction "PE10_63") (pintype "bidirectional"))
    )
    (net (code "86") (name "/PE11") (class "Default")
      (node (ref "U1") (pin "64") (pinfunction "PE11_64") (pintype "bidirectional"))
    )
    (net (code "87") (name "/PE12") (class "Default")
      (node (ref "U1") (pin "65") (pinfunction "PE12_65") (pintype "bidirectional"))
    )
    (net (code "88") (name "/PE13") (class "Default")
      (node (ref "U1") (pin "66") (pinfunction "PE13_66") (pintype "bidirectional"))
    )
    (net (code "89") (name "/PE14") (class "Default")
      (node (ref "U1") (pin "67") (pinfunction "PE14_67") (pintype "bidirectional"))
    )
    (net (code "90") (name "/PE15") (class "Default")
      (node (ref "U1") (pin "68") (pinfunction "PE15_68") (pintype "bidirectional"))
    )
    (net (code "92") (name "/PF0") (class "Default")
      (node (ref "U1") (pin "10") (pinfunction "PF0_10") (pintype "bidirectional"))
    )
    (net (code "93") (name "/PF1") (class "Default")
      (node (ref "U1") (pin "11") (pinfunction "PF1_11") (pintype "bidirectional"))
    )
    (net (code "94") (name "/PF2") (class "Default")
      (node (ref "U1") (pin "12") (pinfunction "PF2_12") (pintype "bidirectional"))
    )
    (net (code "95") (name "/PF3") (class "Default")
      (node (ref "U1") (pin "13") (pinfunction "PF3_13") (pintype "bidirectional"))
    )
    (net (code "96") (name "/PF4") (class "Default")
      (node (ref "U1") (pin "14") (pinfunction "PF4_14") (pintype "bidirectional"))
    )
    (net (code "97") (name "/PF5") (class "Default")
      (node (ref "U1") (pin "15") (pinfunction "PF5_15") (pintype "bidirectional"))
    )
    (net (code "98") (name "/PF6") (class "Default")
      (node (ref "U1") (pin "18") (pinfunction "PF6_18") (pintype "bidirectional"))
    )
    (net (code "99") (name "/PF7") (class "Default")
      (node (ref "U1") (pin "19") (pinfunction "PF7_19") (pintype "bidirectional"))
    )
    (net (code "100") (name "/PF8") (class "Default")
      (node (ref "U1") (pin "20") (pinfunction "PF8_20") (pintype "bidirectional"))
    )
    (net (code "101") (name "/PF9") (class "Default")
      (node (ref "U1") (pin "21") (pinfunction "PF9_21") (pintype "bidirectional"))
    )
    (net (code "102") (name "/PF10") (class "Default")
      (node (ref "U1") (pin "22") (pinfunction "PF10_22") (pintype "bidirectional"))
    )
    (net (code "103") (name "/PF11") (class "Default")
      (node (ref "U1") (pin "49") (pinfunction "PF11_49") (pintype "bidirectional"))
    )
    (net (code "104") (name "/PF12") (class "Default")
      (node (ref "U1") (pin "50") (pinfunction "PF12_50") (pintype "bidirectional"))
    )
    (net (code "105") (name "/PF13") (class "Default")
      (node (ref "U1") (pin "53") (pinfunction "PF13_53") (pintype "bidirectional"))
    )
    (net (code "106") (name "/PF14") (class "Default")
      (node (ref "U1") (pin "54") (pinfunction "PF14_54") (pintype "bidirectional"))
    )
    (net (code "107") (name "/PF15") (class "Default")
      (node (ref "U1") (pin "55") (pinfunction "PF15_55") (pintype "bidirectional"))
    )
    (net (code "109") (name "/PG0") (class "Default")
      (node (ref "U1") (pin "56") (pinfunction "PG0_56") (pintype "bidirectional"))
    )
    (net (code "110") (name "/PG1") (class "Default")
      (node (ref "U1") (pin "57") (pinfunction "PG1_57") (pintype "bidirectional"))
    )
    (net (code "111") (name "/PG2") (class "Default")
      (node (ref "U1") (pin "87") (pinfunction "PG2_87") (pintype "bidirectional"))
    )
    (net (code "112") (name "/PG3") (class "Default")
      (node (ref "U1") (pin "88") (pinfunction "PG3_88") (pintype "bidirectional"))
    )
    (net (code "113") (name "/PG4") (class "Default")
      (node (ref "U1") (pin "89") (pinfunction "PG4_89") (pintype "bidirectional"))
    )
    (net (code "114") (name "/PG5") (class "Default")
      (node (ref "U1") (pin "90") (pinfunction "PG5_90") (pintype "bidirectional"))
    )
    (net (code "115") (name "/PG6") (class "Default")
      (node (ref "U1") (pin "91") (pinfunction "PG6_91") (pintype "bidirectional"))
    )
    (net (code "116") (name "/PG7") (class "Default")
      (node (ref "U1") (pin "92") (pinfunction "PG7_92") (pintype "bidirectional"))
    )
    (net (code "117") (name "/PG8") (class "Default")
      (node (ref "U1") (pin "93") (pinfunction "PG8_93") (pintype "bidirectional"))
    )
    (net (code "118") (name "/PG9") (class "Default")
      (node (ref "U1") (pin "124") (pinfunction "PG9_124") (pintype "bidirectional"))
    )
    (net (code "119") (name "/PG10") (class "Default")
      (node (ref "U1") (pin "125") (pinfunction "PG10_125") (pintype "bidirectional"))
    )
    (net (code "120") (name "/PG11") (class "Default")
      (node (ref "U1") (pin "126") (pinfunction "PG11_126") (pintype "bidirectional"))
    )
    (net (code "121") (name "/PG12") (class "Default")
      (node (ref "U1") (pin "127") (pinfunction "PG12_127") (pintype "bidirectional"))
    )
    (net (code "122") (name "/PG13") (class "Default")
      (node (ref "U1") (pin "128") (pinfunction "PG13_128") (pintype "bidirectional"))
    )
    (net (code "123") (name "/PG14") (class "Default")
      (node (ref "U1") (pin "129") (pinfunction "PG14_129") (pintype "bidirectional"))
    )
    (net (code "124") (name "/PG15") (class "Default")
      (node (ref "U1") (pin "132") (pinfunction "PG15_132") (pintype "bidirectional"))
    )
    (net (code "126") (name "/UART_RX") (class "Default")
      (node (ref "U1") (pin "102") (pinfunction "PA10_102") (pintype "bidirectional"))
    )
    (net (code "127") (name "/UART_TX") (class "Default")
      (node (ref "U1") (pin "101") (pinfunction "PA9_101") (pintype "bidirectional"))
    )
    (net (code "128") (name "GND") (class "Default")
      (node (ref "C10") (pin "2") (pinfunction "2_2") (pintype "passive"))
      (node (ref "C11") (pin "2") (pinfunction "2_2") (pintype "passive"))
      (node (ref "C12") (pin "2") (pinfunction "2_2") (pintype "passive"))
      (node (ref "C13") (pin "2") (pinfunction "2_2") (pintype "passive"))
      (node (ref "C18") (pin "2") (pinfunction "2_2") (pintype "passive"))
      (node (ref "C19") (pin "2") (pinfunction "2_2") (pintype "passive"))
      (node (ref "C20") (pin "2") (pinfunction "2_2") (pintype "passive"))
      (node (ref "C21") (pin "2") (pinfunction "2_2") (pintype "passive"))
      (node (ref "C22") (pin "2") (pinfunction "2_2") (pintype "passive"))
      (node (ref "C4") (pin "2") (pinfunction "2_2") (pintype "passive"))
      (node (ref "C5") (pin "2") (pinfunction "2_2") (pintype "passive"))
      (node (ref "C6") (pin "2") (pinfunction "2_2") (pintype "passive"))
      (node (ref "C7") (pin "2") (pinfunction "2_2") (pintype "passive"))
      (node (ref "C8") (pin "2") (pinfunction "2_2") (pintype "passive"))
      (node (ref "C85") (pin "2") (pinfunction "2_2") (pintype "passive"))
      (node (ref "C86") (pin "2") (pinfunction "2_2") (pintype "passive"))
      (node (ref "C87") (pin "2") (pinfunction "2_2") (pintype "passive"))
      (node (ref "C88") (pin "2") (pinfunction "2_2") (pintype "passive"))
      (node (ref "C89") (pin "2") (pinfunction "2_2") (pintype "passive"))
      (node (ref "C9") (pin "2") (pinfunction "2_2") (pintype "passive"))
      (node (ref "C90") (pin "2") (pinfunction "2_2") (pintype "passive"))
      (node (ref "C91") (pin "2") (pinfunction "2_2") (pintype "passive"))
      (node (ref "C92") (pin "2") (pinfunction "2_2") (pintype "passive"))
      (node (ref "C93") (pin "2") (pinfunction "2_2") (pintype "passive"))
      (node (ref "D3") (pin "1") (pinfunction "1_1") (pintype "passive"))
      (node (ref "D4") (pin "2") (pinfunction "2_2") (pintype "passive"))
      (node (ref "J3") (pin "11") (pinfunction "11_11") (pintype "passive"))
      (node (ref "J3") (pin "5") (pinfunction "5_5") (pintype "passive"))
      (node (ref "J3") (pin "7") (pinfunction "7_7") (pintype "passive"))
      (node (ref "Q1") (pin "2") (pinfunction "source_2") (pintype "passive"))
      (node (ref "R1") (pin "2") (pinfunction "2_2") (pintype "passive"))
      (node (ref "R12") (pin "1") (pinfunction "1_1") (pintype "passive"))
      (node (ref "U1") (pin "107") (pinfunction "VSS_107") (pintype "power_in"))
      (node (ref "U1") (pin "120") (pinfunction "VSS_120") (pintype "power_in"))
      (node (ref "U1") (pin "130") (pinfunction "VSS_130") (pintype "power_in"))
      (node (ref "U1") (pin "16") (pinfunction "VSS_16") (pintype "power_in"))
      (node (ref "U1") (pin "31") (pinfunction "VSSA_31") (pintype "power_in"))
      (node (ref "U1") (pin "38") (pinfunction "VSS_38") (pintype "power_in"))
      (node (ref "U1") (pin "51") (pinfunction "VSS_51") (pintype "power_in"))
      (node (ref "U1") (pin "61") (pinfunction "VSS_61") (pintype "power_in"))
      (node (ref "U1") (pin "83") (pinfunction "VSS_83") (pintype "power_in"))
      (node (ref "U1") (pin "94") (pinfunction "VSS_94") (pintype "power_in"))
      (node (ref "Y1") (pin "2") (pinfunction "GND_2") (pintype "power_in"))
      (node (ref "Y1") (pin "4") (pinfunction "GND_4") (pintype "power_in"))
    )
    (net (code "129") (name "Net-(C3-Pad2)") (class "Default")
      (node (ref "C3") (pin "2") (pinfunction "2_2") (pintype "passive"))
      (node (ref "D3") (pin "2") (pinfunction "2_2") (pintype "passive"))
      (node (ref "SW1") (pin "1") (pinfunction "1_1") (pintype "passive"))
      (node (ref "SW1") (pin "2") (pinfunction "2_2") (pintype "passive"))
    )
    (net (code "130") (name "Net-(D2-A)") (class "Default")
      (node (ref "D2") (pin "2") (pinfunction "A_2") (pintype "passive"))
      (node (ref "R5") (pin "1") (pinfunction "1_1") (pintype "passive"))
    )
    (net (code "131") (name "Net-(D2-C)") (class "Default")
      (node (ref "D2") (pin "1") (pinfunction "C_1") (pintype "passive"))
      (node (ref "Q1") (pin "3") (pinfunction "drain_3") (pintype "passive"))
    )
    (net (code "132") (name "Net-(S1-NO)") (class "Default")
      (node (ref "D4") (pin "1") (pinfunction "1_1") (pintype "passive"))
      (node (ref "S1") (pin "3") (pinfunction "NO_3") (pintype "passive"))
    )
    (net (code "133") (name "unconnected-(J3-Pad1)") (class "Default")
      (node (ref "J3") (pin "1") (pinfunction "1_1") (pintype "passive+no_connect"))
    )
    (net (code "134") (name "unconnected-(J3-Pad2)") (class "Default")
      (node (ref "J3") (pin "2") (pinfunction "2_2") (pintype "passive+no_connect"))
    )
    (net (code "135") (name "unconnected-(J3-Pad9)") (class "Default")
      (node (ref "J3") (pin "9") (pinfunction "9_9") (pintype "passive+no_connect"))
    )
    (net (code "136") (name "unconnected-(J3-Pad10)") (class "Default")
      (node (ref "J3") (pin "10") (pinfunction "10_10") (pintype "passive+no_connect"))
    )
    (net (code "137") (name "unconnected-(J3-Pad12)") (class "Default")
      (node (ref "J3") (pin "12") (pinfunction "12_12") (pintype "passive+no_connect"))
    )
    (net (code "138") (name "unconnected-(J3-Pad13)") (class "Default")
      (node (ref "J3") (pin "13") (pinfunction "13_13") (pintype "passive+no_connect"))
    )
    (net (code "139") (name "unconnected-(J3-Pad14)") (class "Default")
      (node (ref "J3") (pin "14") (pinfunction "14_14") (pintype "passive+no_connect"))
    )
    (net (code "140") (name "unconnected-(S1-PadMP1)") (class "Default")
      (node (ref "S1") (pin "MP1") (pinfunction "MP1_MP1") (pintype "passive+no_connect"))
    )
    (net (code "141") (name "unconnected-(S1-PadMP2)") (class "Default")
      (node (ref "S1") (pin "MP2") (pinfunction "MP2_MP2") (pintype "passive+no_connect"))
    )
    (net (code "142") (name "unconnected-(S1-PadMP3)") (class "Default")
      (node (ref "S1") (pin "MP3") (pinfunction "MP3_MP3") (pintype "passive+no_connect"))
    )
    (net (code "143") (name "unconnected-(S1-PadMP4)") (class "Default")
      (node (ref "S1") (pin "MP4") (pinfunction "MP4_MP4") (pintype "passive+no_connect"))
    )
    (net (code "144") (name "unconnected-(U1B-PA15-Pad110)") (class "Default")
      (node (ref "U1") (pin "110") (pinfunction "PA15_110") (pintype "bidirectional+no_connect"))
    )
    (net (code "145") (name "unconnected-(U1B-PB4-Pad134)") (class "Default")
      (node (ref "U1") (pin "134") (pinfunction "PB4_134") (pintype "bidirectional+no_connect"))
    )
  )
)
